# Schemat_top.net
KiCad netlist of a schematic drawn in Altium Designer
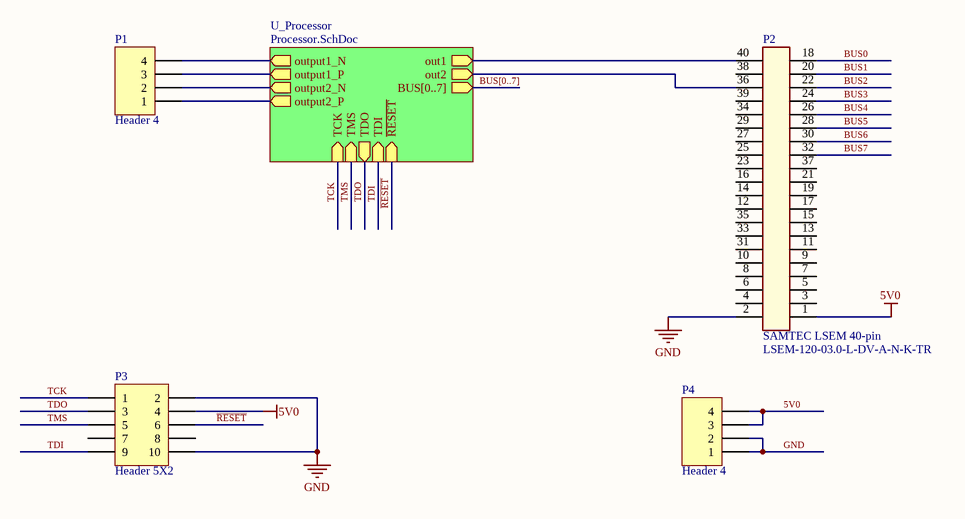
[diagram p0: Schemat_top.SchDoc]

(export (version "E")
  (design (tool "Eeschema 10.0.6"))
  (components
    (comp (ref "P1")
      (value "Header 4")
      (footprint "HDR1X4")
      (description "Header, 4-Pin")
      (fields (field (name "PUBLISHER") "Altium Limited"))
      (libsource (lib "Miscellaneous Connectors") (part "Header 4"))
    )
    (comp (ref "P2")
      (value "SAMTEC LSEM 40-pin")
      (footprint "LSEM-120-03.0-L-DV-A-N-K-TR")
      (description "Component desciption")
      (fields (field (name "PART NUMBER") "LSEM-120-03.0-L-DV-A-N-K-TR"))
      (libsource (lib "Schematic_Library_TK") (part "SAMTEC LSEM 40-pin"))
    )
    (comp (ref "P3")
      (value "Header 5X2")
      (footprint "HDR2X5")
      (description "Header, 5-Pin, Dual row")
      (fields (field (name "PUBLISHER") "Altium Limited"))
      (libsource (lib "Miscellaneous Connectors") (part "Header 5X2"))
    )
    (comp (ref "P4")
      (value "Header 4")
      (footprint "HDR1X4")
      (description "Header, 4-Pin")
      (fields (field (name "PUBLISHER") "Altium Limited"))
      (libsource (lib "Miscellaneous Connectors") (part "Header 4"))
    )
  )
  (nets
    (net (code "1") (name "/BUS0") (class "Default")
      (node (ref "P2") (pin "18") (pinfunction "10_18") (pintype "passive"))
    )
    (net (code "2") (name "/BUS1") (class "Default")
      (node (ref "P2") (pin "20") (pinfunction "11_20") (pintype "passive"))
    )
    (net (code "3") (name "/BUS2") (class "Default")
      (node (ref "P2") (pin "22") (pinfunction "12_22") (pintype "passive"))
    )
    (net (code "4") (name "/BUS3") (class "Default")
      (node (ref "P2") (pin "24") (pinfunction "13_24") (pintype "passive"))
    )
    (net (code "5") (name "/BUS4") (class "Default")
      (node (ref "P2") (pin "26") (pinfunction "14_26") (pintype "passive"))
    )
    (net (code "6") (name "/BUS5") (class "Default")
      (node (ref "P2") (pin "28") (pinfunction "15_28") (pintype "passive"))
    )
    (net (code "7") (name "/BUS6") (class "Default")
      (node (ref "P2") (pin "30") (pinfunction "16_30") (pintype "passive"))
    )
    (net (code "8") (name "/BUS7") (class "Default")
      (node (ref "P2") (pin "32") (pinfunction "17_32") (pintype "passive"))
    )
    (net (code "10") (name "/TCK") (class "Default")
      (node (ref "P3") (pin "1") (pinfunction "1_1") (pintype "passive"))
    )
    (net (code "11") (name "/TDI") (class "Default")
      (node (ref "P3") (pin "9") (pinfunction "9_9") (pintype "passive"))
    )
    (net (code "12") (name "/TDO") (class "Default")
      (node (ref "P3") (pin "3") (pinfunction "3_3") (pintype "passive"))
    )
    (net (code "13") (name "/TMS") (class "Default")
      (node (ref "P3") (pin "5") (pinfunction "5_5") (pintype "passive"))
    )
    (net (code "14") (name "/out1") (class "Default")
      (node (ref "P2") (pin "40") (pinfunction "21_40") (pintype "passive"))
    )
    (net (code "15") (name "/out2") (class "Default")
      (node (ref "P2") (pin "36") (pinfunction "19_36") (pintype "passive"))
    )
    (net (code "16") (name "/output1_N") (class "Default")
      (node (ref "P1") (pin "4") (pinfunction "4_4") (pintype "passive"))
    )
    (net (code "17") (name "/output1_P") (class "Default")
      (node (ref "P1") (pin "3") (pinfunction "3_3") (pintype "passive"))
    )
    (net (code "18") (name "/output2_N") (class "Default")
      (node (ref "P1") (pin "2") (pinfunction "2_2") (pintype "passive"))
    )
    (net (code "19") (name "/output2_P") (class "Default")
      (node (ref "P1") (pin "1") (pinfunction "1_1") (pintype "passive"))
    )
    (net (code "20") (name "/~{RESET}") (class "Default")
      (node (ref "P3") (pin "6") (pinfunction "6_6") (pintype "passive"))
    )
    (net (code "21") (name "5V0") (class "Default")
      (node (ref "P2") (pin "1") (pinfunction "PIN_1") (pintype "passive"))
      (node (ref "P3") (pin "4") (pinfunction "4_4") (pintype "passive"))
      (node (ref "P4") (pin "3") (pinfunction "3_3") (pintype "passive"))
      (node (ref "P4") (pin "4") (pinfunction "4_4") (pintype "passive"))
    )
    (net (code "22") (name "GND") (class "Default")
      (node (ref "P2") (pin "2") (pinfunction "2_2") (pintype "passive"))
      (node (ref "P3") (pin "10") (pinfunction "10_10") (pintype "passive"))
      (node (ref "P3") (pin "2") (pinfunction "2_2") (pintype "passive"))
      (node (ref "P4") (pin "1") (pinfunction "1_1") (pintype "passive"))
      (node (ref "P4") (pin "2") (pinfunction "2_2") (pintype "passive"))
    )
    (net (code "23") (name "unconnected-(P2-3-Pad4)") (class "Default")
      (node (ref "P2") (pin "4") (pinfunction "3_4") (pintype "passive"))
    )
    (net (code "24") (name "unconnected-(P2-4-Pad6)") (class "Default")
      (node (ref "P2") (pin "6") (pinfunction "4_6") (pintype "passive"))
    )
    (net (code "25") (name "unconnected-(P2-5-Pad8)") (class "Default")
      (node (ref "P2") (pin "8") (pinfunction "5_8") (pintype "passive"))
    )
    (net (code "26") (name "unconnected-(P2-6-Pad10)") (class "Default")
      (node (ref "P2") (pin "10") (pinfunction "6_10") (pintype "passive"))
    )
    (net (code "27") (name "unconnected-(P2-7-Pad12)") (class "Default")
      (node (ref "P2") (pin "12") (pinfunction "7_12") (pintype "passive"))
    )
    (net (code "28") (name "unconnected-(P2-8-Pad14)") (class "Default")
      (node (ref "P2") (pin "14") (pinfunction "8_14") (pintype "passive"))
    )
    (net (code "29") (name "unconnected-(P2-9-Pad16)") (class "Default")
      (node (ref "P2") (pin "16") (pinfunction "9_16") (pintype "passive"))
    )
    (net (code "30") (name "unconnected-(P2-18-Pad34)") (class "Default")
      (node (ref "P2") (pin "34") (pinfunction "18_34") (pintype "passive"))
    )
    (net (code "31") (name "unconnected-(P2-20-Pad38)") (class "Default")
      (node (ref "P2") (pin "38") (pinfunction "20_38") (pintype "passive"))
    )
    (net (code "32") (name "unconnected-(P2-PIN-Pad3)") (class "Default")
      (node (ref "P2") (pin "3") (pinfunction "PIN_3") (pintype "passive"))
    )
    (net (code "33") (name "unconnected-(P2-PIN-Pad5)") (class "Default")
      (node (ref "P2") (pin "5") (pinfunction "PIN_5") (pintype "passive"))
    )
    (net (code "34") (name "unconnected-(P2-PIN-Pad7)") (class "Default")
      (node (ref "P2") (pin "7") (pinfunction "PIN_7") (pintype "passive"))
    )
    (net (code "35") (name "unconnected-(P2-PIN-Pad9)") (class "Default")
      (node (ref "P2") (pin "9") (pinfunction "PIN_9") (pintype "passive"))
    )
    (net (code "36") (name "unconnected-(P2-PIN-Pad11)") (class "Default")
      (node (ref "P2") (pin "11") (pinfunction "PIN_11") (pintype "passive"))
    )
    (net (code "37") (name "unconnected-(P2-PIN-Pad13)") (class "Default")
      (node (ref "P2") (pin "13") (pinfunction "PIN_13") (pintype "passive"))
    )
    (net (code "38") (name "unconnected-(P2-PIN-Pad15)") (class "Default")
      (node (ref "P2") (pin "15") (pinfunction "PIN_15") (pintype "passive"))
    )
    (net (code "39") (name "unconnected-(P2-PIN-Pad17)") (class "Default")
      (node (ref "P2") (pin "17") (pinfunction "PIN_17") (pintype "passive"))
    )
    (net (code "40") (name "unconnected-(P2-PIN-Pad19)") (class "Default")
      (node (ref "P2") (pin "19") (pinfunction "PIN_19") (pintype "passive"))
    )
    (net (code "41") (name "unconnected-(P2-PIN-Pad21)") (class "Default")
      (node (ref "P2") (pin "21") (pinfunction "PIN_21") (pintype "passive"))
    )
    (net (code "42") (name "unconnected-(P2-PIN-Pad23)") (class "Default")
      (node (ref "P2") (pin "23") (pinfunction "PIN_23") (pintype "passive"))
    )
    (net (code "43") (name "unconnected-(P2-PIN-Pad25)") (class "Default")
      (node (ref "P2") (pin "25") (pinfunction "PIN_25") (pintype "passive"))
    )
    (net (code "44") (name "unconnected-(P2-PIN-Pad27)") (class "Default")
      (node (ref "P2") (pin "27") (pinfunction "PIN_27") (pintype "passive"))
    )
    (net (code "45") (name "unconnected-(P2-PIN-Pad29)") (class "Default")
      (node (ref "P2") (pin "29") (pinfunction "PIN_29") (pintype "passive"))
    )
    (net (code "46") (name "unconnected-(P2-PIN-Pad31)") (class "Default")
      (node (ref "P2") (pin "31") (pinfunction "PIN_31") (pintype "passive"))
    )
    (net (code "47") (name "unconnected-(P2-PIN-Pad33)") (class "Default")
      (node (ref "P2") (pin "33") (pinfunction "PIN_33") (pintype "passive"))
    )
    (net (code "48") (name "unconnected-(P2-PIN-Pad35)") (class "Default")
      (node (ref "P2") (pin "35") (pinfunction "PIN_35") (pintype "passive"))
    )
    (net (code "49") (name "unconnected-(P2-PIN-Pad37)") (class "Default")
      (node (ref "P2") (pin "37") (pinfunction "PIN_37") (pintype "passive"))
    )
    (net (code "50") (name "unconnected-(P2-PIN-Pad39)") (class "Default")
      (node (ref "P2") (pin "39") (pinfunction "PIN_39") (pintype "passive"))
    )
    (net (code "51") (name "unconnected-(P3-Pad7)") (class "Default")
      (node (ref "P3") (pin "7") (pinfunction "7_7") (pintype "passive"))
    )
    (net (code "52") (name "unconnected-(P3-Pad8)") (class "Default")
      (node (ref "P3") (pin "8") (pinfunction "8_8") (pintype "passive"))
    )
  )
)
